# KidMotorV1_1.net
KiCad netlist of a schematic drawn in EAGLE
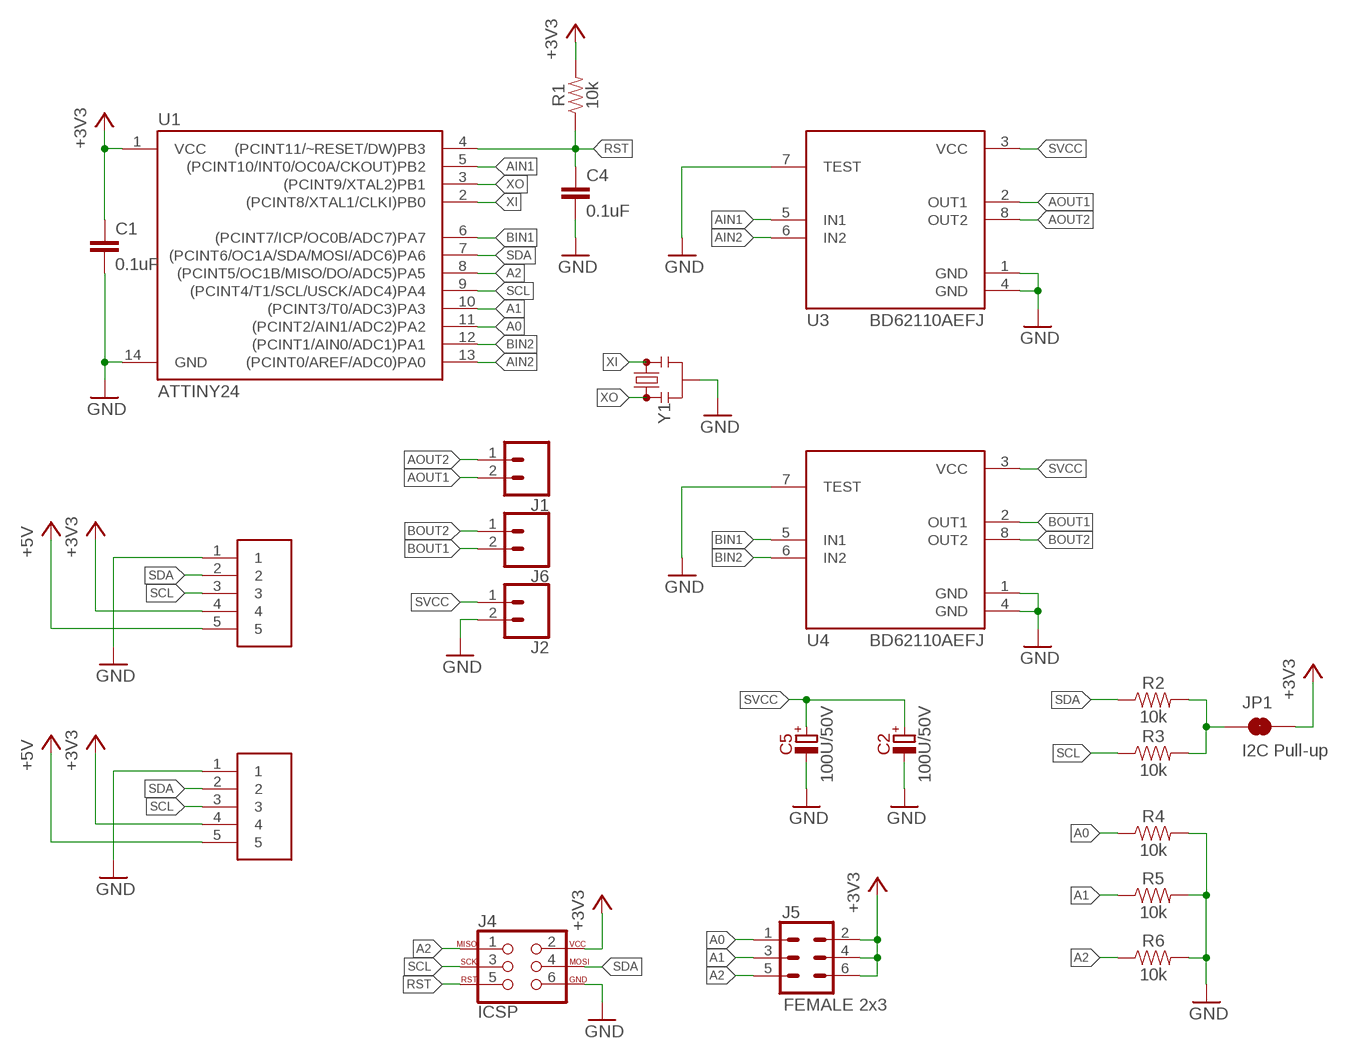
[diagram p0: schematic, sheet 1]

(export (version "E")
  (design (tool "Eeschema 10.0.6"))
  (components
    (comp (ref "C1")
      (value "0.1uF")
      (footprint "eagle-import:0603")
      (libsource (lib "eagle-import") (part "1.0UF-0603-16V-10%"))
    )
    (comp (ref "C2")
      (value "100U/50V")
      (footprint "eagle-import:E3,5-8")
      (libsource (lib "eagle-import") (part "?100U/50V"))
    )
    (comp (ref "C4")
      (value "0.1uF")
      (footprint "eagle-import:0603")
      (libsource (lib "eagle-import") (part "0.1UF-0603-25V-5%"))
    )
    (comp (ref "C5")
      (value "100U/50V")
      (footprint "eagle-import:E3,5-8")
      (libsource (lib "eagle-import") (part "?100U/50V"))
    )
    (comp (ref "J1")
      (value "CONN_025MM")
      (footprint "eagle-import:SCREWTERMINAL-5MM-2")
      (libsource (lib "eagle-import") (part "CONN_025MM"))
    )
    (comp (ref "J2")
      (value "CONN_025MM")
      (footprint "eagle-import:SCREWTERMINAL-5MM-2")
      (libsource (lib "eagle-import") (part "CONN_025MM"))
    )
    (comp (ref "J4")
      (value "ICSP")
      (footprint "eagle-import:2X3")
      (libsource (lib "eagle-import") (part "AVR_SPI_PROG_3X2PTH"))
    )
    (comp (ref "J5")
      (value "FEMALE 2x3")
      (footprint "eagle-import:2X3")
      (libsource (lib "eagle-import") (part "CONN_03X2FEMALE"))
    )
    (comp (ref "J6")
      (value "CONN_025MM")
      (footprint "eagle-import:SCREWTERMINAL-5MM-2")
      (libsource (lib "eagle-import") (part "CONN_025MM"))
    )
    (comp (ref "JP1")
      (value "I2C Pull-up")
      (footprint "eagle-import:SMT-JUMPER_2_NC_TRACE_SILK")
      (libsource (lib "eagle-import") (part "JUMPER-SMT_2_NC_TRACE_SILK"))
    )
    (comp (ref "R1")
      (value "10k")
      (footprint "eagle-import:0603")
      (libsource (lib "eagle-import") (part "10KOHM-0603-1/10W-1%"))
    )
    (comp (ref "R2")
      (value "10k")
      (footprint "eagle-import:0603")
      (libsource (lib "eagle-import") (part "10KOHM-0603-1/10W-1%"))
    )
    (comp (ref "R3")
      (value "10k")
      (footprint "eagle-import:0603")
      (libsource (lib "eagle-import") (part "10KOHM-0603-1/10W-1%"))
    )
    (comp (ref "R4")
      (value "10k")
      (footprint "eagle-import:0603")
      (libsource (lib "eagle-import") (part "10KOHM-0603-1/10W-1%"))
    )
    (comp (ref "R5")
      (value "10k")
      (footprint "eagle-import:0603")
      (libsource (lib "eagle-import") (part "10KOHM-0603-1/10W-1%"))
    )
    (comp (ref "R6")
      (value "10k")
      (footprint "eagle-import:0603")
      (libsource (lib "eagle-import") (part "10KOHM-0603-1/10W-1%"))
    )
    (comp (ref "U$2")
      (value "JST5PIN")
      (footprint "eagle-import:JST5PIN")
      (libsource (lib "eagle-import") (part "JST5PIN"))
    )
    (comp (ref "U$5")
      (value "JST5PIN")
      (footprint "eagle-import:JST5PIN")
      (libsource (lib "eagle-import") (part "JST5PIN"))
    )
    (comp (ref "U1")
      (value "ATTINY24")
      (footprint "eagle-import:SO14")
      (libsource (lib "eagle-import") (part "ATTINY84"))
    )
    (comp (ref "U3")
      (value "BD62110AEFJ")
      (footprint "eagle-import:HTSOP-J8")
      (libsource (lib "eagle-import") (part "BD62110AEFJ"))
    )
    (comp (ref "U4")
      (value "BD62110AEFJ")
      (footprint "eagle-import:HTSOP-J8")
      (libsource (lib "eagle-import") (part "BD62110AEFJ"))
    )
    (comp (ref "Y1")
      (value "RESONATORSMD-3.2X1.3")
      (footprint "eagle-import:RESONATOR-SMD-3.2X1.3")
      (libsource (lib "eagle-import") (part "RESONATORSMD-3.2X1.3"))
    )
  )
  (nets
    (net (code "1") (name "+3V3") (class "Default")
      (node (ref "C1") (pin "1") (pinfunction "1_1") (pintype "passive"))
      (node (ref "J4") (pin "2") (pinfunction "2_2") (pintype "passive"))
      (node (ref "J5") (pin "2") (pinfunction "2_2") (pintype "bidirectional"))
      (node (ref "J5") (pin "4") (pinfunction "4_4") (pintype "bidirectional"))
      (node (ref "J5") (pin "6") (pinfunction "6_6") (pintype "bidirectional"))
      (node (ref "JP1") (pin "2") (pinfunction "2_2") (pintype "passive"))
      (node (ref "R1") (pin "2") (pinfunction "2_2") (pintype "passive"))
      (node (ref "U$2") (pin "4") (pinfunction "4_4") (pintype "bidirectional"))
      (node (ref "U$5") (pin "4") (pinfunction "4_4") (pintype "bidirectional"))
      (node (ref "U1") (pin "1") (pinfunction "VCC_1") (pintype "bidirectional"))
    )
    (net (code "2") (name "+5V") (class "Default")
      (node (ref "U$2") (pin "5") (pinfunction "5_5") (pintype "bidirectional"))
      (node (ref "U$5") (pin "5") (pinfunction "5_5") (pintype "bidirectional"))
    )
    (net (code "3") (name "A0") (class "Default")
      (node (ref "J5") (pin "1") (pinfunction "1_1") (pintype "bidirectional"))
      (node (ref "R4") (pin "1") (pinfunction "1_1") (pintype "passive"))
      (node (ref "U1") (pin "11") (pinfunction "(PCINT2/AIN1/ADC2)PA2_11") (pintype "bidirectional"))
    )
    (net (code "4") (name "A1") (class "Default")
      (node (ref "J5") (pin "3") (pinfunction "3_3") (pintype "bidirectional"))
      (node (ref "R5") (pin "1") (pinfunction "1_1") (pintype "passive"))
      (node (ref "U1") (pin "10") (pinfunction "(PCINT3/T0/ADC3)PA3_10") (pintype "bidirectional"))
    )
    (net (code "5") (name "A2") (class "Default")
      (node (ref "J4") (pin "1") (pinfunction "1_1") (pintype "passive"))
      (node (ref "J5") (pin "5") (pinfunction "5_5") (pintype "bidirectional"))
      (node (ref "R6") (pin "1") (pinfunction "1_1") (pintype "passive"))
      (node (ref "U1") (pin "8") (pinfunction "(PCINT5/OC1B/MISO/DO/ADC5)PA5_8") (pintype "bidirectional"))
    )
    (net (code "6") (name "AIN1") (class "Default")
      (node (ref "U1") (pin "5") (pinfunction "(PCINT10/INT0/OC0A/CKOUT)PB2_5") (pintype "bidirectional"))
      (node (ref "U3") (pin "5") (pinfunction "IN1_5") (pintype "bidirectional"))
    )
    (net (code "7") (name "AIN2") (class "Default")
      (node (ref "U1") (pin "13") (pinfunction "(PCINT0/AREF/ADC0)PA0_13") (pintype "bidirectional"))
      (node (ref "U3") (pin "6") (pinfunction "IN2_6") (pintype "bidirectional"))
    )
    (net (code "8") (name "AOUT1") (class "Default")
      (node (ref "J1") (pin "2") (pinfunction "2_2") (pintype "passive"))
      (node (ref "U3") (pin "2") (pinfunction "OUT1_2") (pintype "bidirectional"))
    )
    (net (code "9") (name "AOUT2") (class "Default")
      (node (ref "J1") (pin "1") (pinfunction "1_1") (pintype "passive"))
      (node (ref "U3") (pin "8") (pinfunction "OUT2_8") (pintype "bidirectional"))
    )
    (net (code "10") (name "BIN1") (class "Default")
      (node (ref "U1") (pin "6") (pinfunction "(PCINT7/ICP/OC0B/ADC7)PA7_6") (pintype "bidirectional"))
      (node (ref "U4") (pin "5") (pinfunction "IN1_5") (pintype "bidirectional"))
    )
    (net (code "11") (name "BIN2") (class "Default")
      (node (ref "U1") (pin "12") (pinfunction "(PCINT1/AIN0/ADC1)PA1_12") (pintype "bidirectional"))
      (node (ref "U4") (pin "6") (pinfunction "IN2_6") (pintype "bidirectional"))
    )
    (net (code "12") (name "BOUT1") (class "Default")
      (node (ref "J6") (pin "2") (pinfunction "2_2") (pintype "passive"))
      (node (ref "U4") (pin "2") (pinfunction "OUT1_2") (pintype "bidirectional"))
    )
    (net (code "13") (name "BOUT2") (class "Default")
      (node (ref "J6") (pin "1") (pinfunction "1_1") (pintype "passive"))
      (node (ref "U4") (pin "8") (pinfunction "OUT2_8") (pintype "bidirectional"))
    )
    (net (code "14") (name "GND") (class "Default")
      (node (ref "C1") (pin "2") (pinfunction "2_2") (pintype "passive"))
      (node (ref "C2") (pin "-") (pinfunction "-_-") (pintype "passive"))
      (node (ref "C4") (pin "2") (pinfunction "2_2") (pintype "passive"))
      (node (ref "C5") (pin "-") (pinfunction "-_-") (pintype "passive"))
      (node (ref "J2") (pin "2") (pinfunction "2_2") (pintype "passive"))
      (node (ref "J4") (pin "6") (pinfunction "6_6") (pintype "passive"))
      (node (ref "R4") (pin "2") (pinfunction "2_2") (pintype "passive"))
      (node (ref "R5") (pin "2") (pinfunction "2_2") (pintype "passive"))
      (node (ref "R6") (pin "2") (pinfunction "2_2") (pintype "passive"))
      (node (ref "U$2") (pin "1") (pinfunction "1_1") (pintype "bidirectional"))
      (node (ref "U$5") (pin "1") (pinfunction "1_1") (pintype "bidirectional"))
      (node (ref "U1") (pin "14") (pinfunction "GND_14") (pintype "bidirectional"))
      (node (ref "U3") (pin "1") (pinfunction "GND_1") (pintype "bidirectional"))
      (node (ref "U3") (pin "4") (pinfunction "GND_4") (pintype "bidirectional"))
      (node (ref "U3") (pin "7") (pinfunction "TEST_7") (pintype "bidirectional"))
      (node (ref "U4") (pin "1") (pinfunction "GND_1") (pintype "bidirectional"))
      (node (ref "U4") (pin "4") (pinfunction "GND_4") (pintype "bidirectional"))
      (node (ref "U4") (pin "7") (pinfunction "TEST_7") (pintype "bidirectional"))
      (node (ref "Y1") (pin "2") (pinfunction "2_2") (pintype "passive"))
    )
    (net (code "15") (name "Net-(JP1-Pad1)") (class "Default")
      (node (ref "JP1") (pin "1") (pinfunction "1_1") (pintype "passive"))
      (node (ref "R2") (pin "2") (pinfunction "2_2") (pintype "passive"))
      (node (ref "R3") (pin "2") (pinfunction "2_2") (pintype "passive"))
    )
    (net (code "16") (name "RST") (class "Default")
      (node (ref "C4") (pin "1") (pinfunction "1_1") (pintype "passive"))
      (node (ref "J4") (pin "5") (pinfunction "5_5") (pintype "passive"))
      (node (ref "R1") (pin "1") (pinfunction "1_1") (pintype "passive"))
      (node (ref "U1") (pin "4") (pinfunction "(PCINT11/~{RESET/DW})PB3_4") (pintype "bidirectional"))
    )
    (net (code "17") (name "SCL") (class "Default")
      (node (ref "J4") (pin "3") (pinfunction "3_3") (pintype "passive"))
      (node (ref "R3") (pin "1") (pinfunction "1_1") (pintype "passive"))
      (node (ref "U$2") (pin "3") (pinfunction "3_3") (pintype "bidirectional"))
      (node (ref "U$5") (pin "3") (pinfunction "3_3") (pintype "bidirectional"))
      (node (ref "U1") (pin "9") (pinfunction "(PCINT4/T1/SCL/USCK/ADC4)PA4_9") (pintype "bidirectional"))
    )
    (net (code "18") (name "SDA") (class "Default")
      (node (ref "J4") (pin "4") (pinfunction "4_4") (pintype "passive"))
      (node (ref "R2") (pin "1") (pinfunction "1_1") (pintype "passive"))
      (node (ref "U$2") (pin "2") (pinfunction "2_2") (pintype "bidirectional"))
      (node (ref "U$5") (pin "2") (pinfunction "2_2") (pintype "bidirectional"))
      (node (ref "U1") (pin "7") (pinfunction "(PCINT6/OC1A/SDA/MOSI/ADC6)PA6_7") (pintype "bidirectional"))
    )
    (net (code "19") (name "SVCC") (class "Default")
      (node (ref "C2") (pin "+") (pinfunction "+_+") (pintype "passive"))
      (node (ref "C5") (pin "+") (pinfunction "+_+") (pintype "passive"))
      (node (ref "J2") (pin "1") (pinfunction "1_1") (pintype "passive"))
      (node (ref "U3") (pin "3") (pinfunction "VCC_3") (pintype "bidirectional"))
      (node (ref "U4") (pin "3") (pinfunction "VCC_3") (pintype "bidirectional"))
    )
    (net (code "20") (name "XI") (class "Default")
      (node (ref "U1") (pin "2") (pinfunction "(PCINT8/XTAL1/CLKI)PB0_2") (pintype "bidirectional"))
      (node (ref "Y1") (pin "3") (pinfunction "3_3") (pintype "passive"))
    )
    (net (code "21") (name "XO") (class "Default")
      (node (ref "U1") (pin "3") (pinfunction "(PCINT9/XTAL2)PB1_3") (pintype "bidirectional"))
      (node (ref "Y1") (pin "1") (pinfunction "1_1") (pintype "passive"))
    )
  )
)
